# 24VloadSwitch.net
KiCad netlist of a schematic drawn in Altium Designer
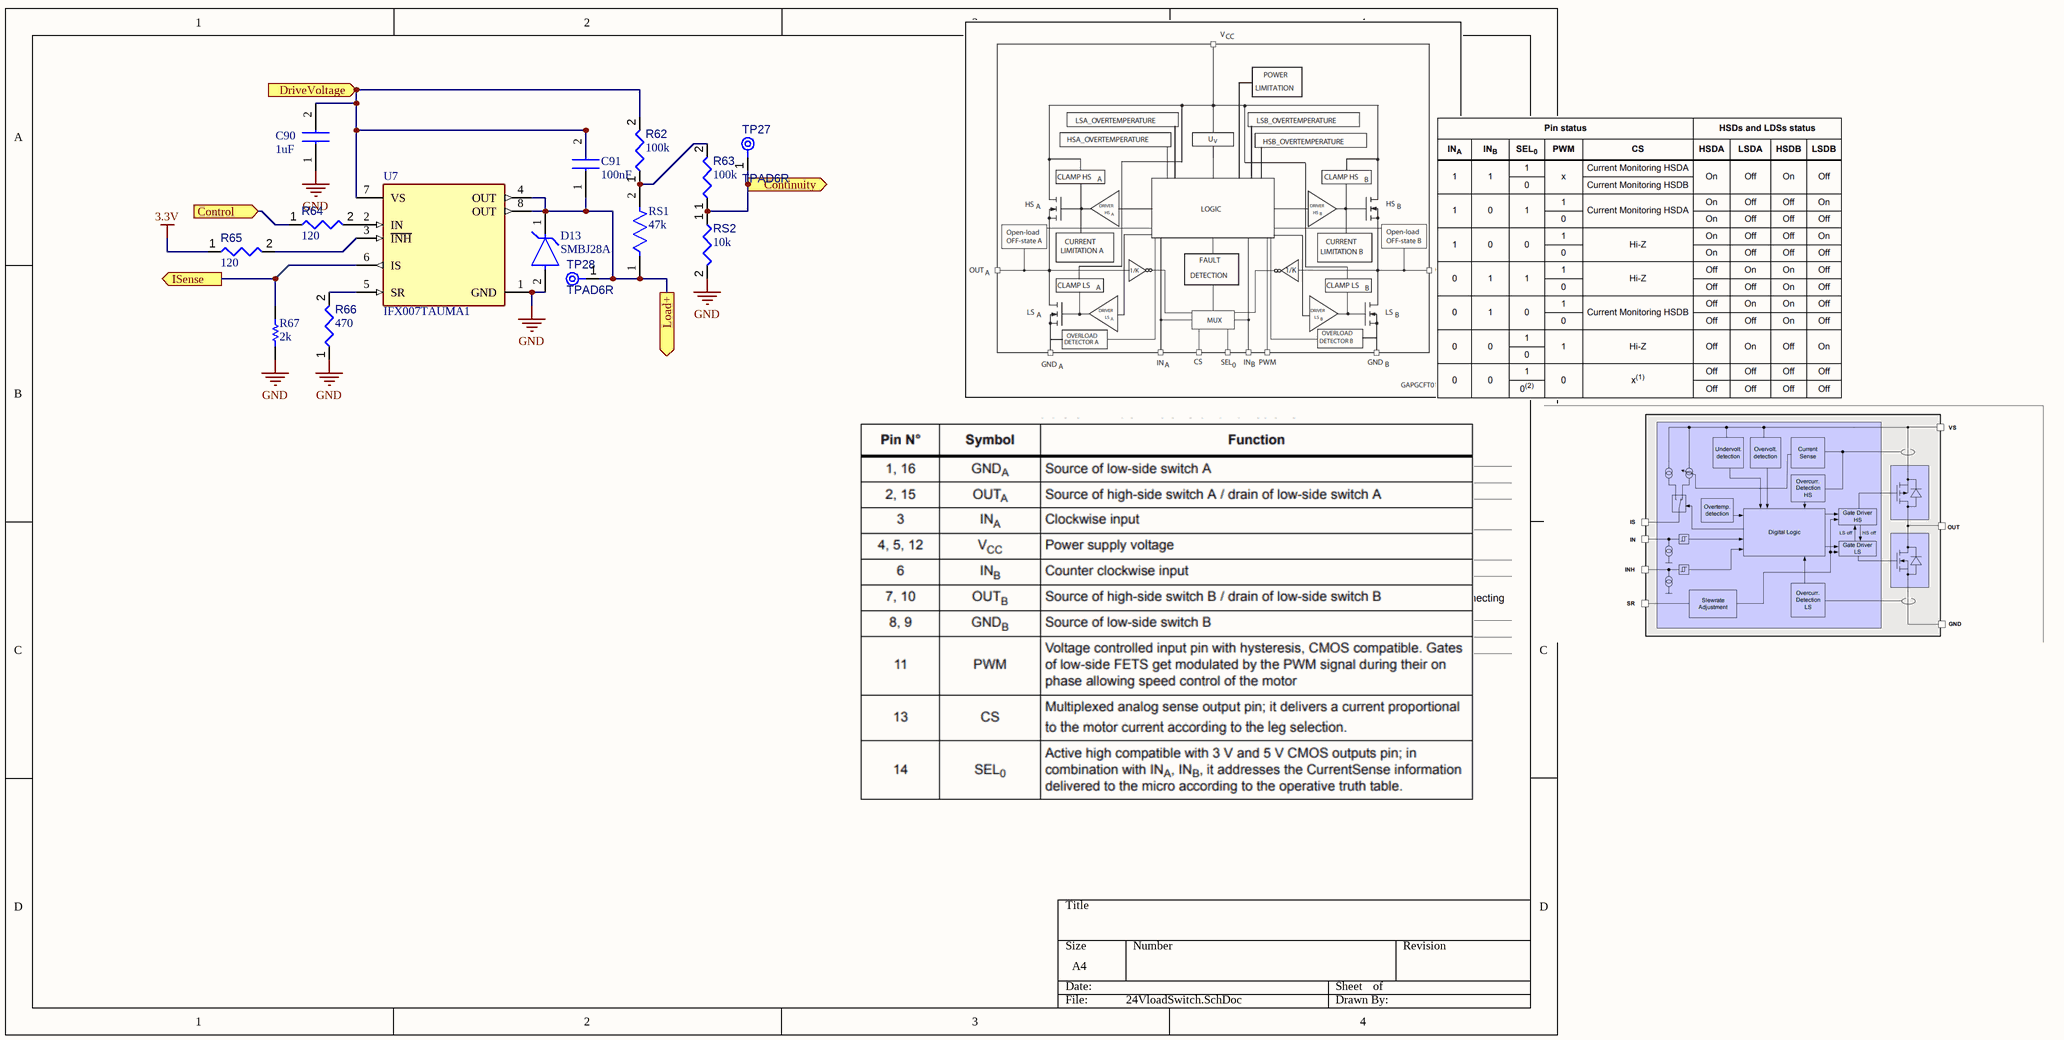
[diagram p0: 24VloadSwitch.SchDoc]

(export (version "E")
  (design (tool "Eeschema 10.0.6"))
  (components
    (comp (ref "C90")
      (value "1uF")
      (footprint "SamacSys:CAPC3216X180N")
      (description "1uF,1206, 50v")
      (fields
        (field (name "MANUFACTURER_PART_NUMBER") "CL31B105KBHNNNE")
        (field (name "MOUSER PART NUMBER") "187-CL31B105KBHNNNE")
      )
      (libsource (lib "*") (part "CL31B105KBHNNNE"))
    )
    (comp (ref "C91")
      (value "100nF")
      (footprint "SamacSys:CAPC1608X90N")
      (description "Capacitor,0603, 50V")
      (fields
        (field (name "MANUFACTURER_PART_NUMBER") "CC0603KRX7R9BB104")
        (field (name "MOUSER PART NUMBER") "603-CC603KRX7R9BB104")
      )
      (libsource (lib "*") (part "CC0603KRX7R9BB104"))
    )
    (comp (ref "D13")
      (value "SMBJ28A")
      (footprint "FP-SMBJ-MFG")
      (description "TVS DIODE 28V 45.4V DO214AA")
      (fields
        (field (name "MANUFACTURER") "Littelfuse Inc")
        (field (name "OCTOPART") "https://octopart.com/smbj28a-littelfuse-350790")
      )
      (libsource (lib "Altium Content Vault") (part "f813f71cba58e380607f5dd3caf9714"))
    )
    (comp (ref "R62")
      (value "100k")
      (footprint "RESC1608X55X25ML10T15")
      (description "Chip Resistor, 100 KOhm, +/- 1%, 0.1 W, -55 to 155 degC, 0603 (1608 Metric)")
      (fields (field (name "TOLERANCE") "1%") (field (name "POWER") "100mW"))
      (libsource (lib "Yuxuan chen") (part "RES-2"))
    )
    (comp (ref "R63")
      (value "100k")
      (footprint "RESC1608X55X25ML10T15")
      (description "Chip Resistor, 100 KOhm, +/- 1%, 0.1 W, -55 to 155 degC, 0603 (1608 Metric)")
      (fields (field (name "TOLERANCE") "1%") (field (name "POWER") "100mW"))
      (libsource (lib "Yuxuan chen") (part "RES-2"))
    )
    (comp (ref "R64")
      (value "120")
      (footprint "RESC0603(1608)_L")
      (description "Chip Resistor, 120 Ohms, +/-5 %, 0.1 W, -55 to 155 degC, 0603")
      (fields (field (name "POWER") "100mW") (field (name "TOLERANCE") "5%"))
      (libsource (lib "Yuxuan chen") (part "RES-2"))
    )
    (comp (ref "R65")
      (value "120")
      (footprint "RESC0603(1608)_L")
      (description "Chip Resistor, 120 Ohms, +/-5 %, 0.1 W, -55 to 155 degC, 0603")
      (fields (field (name "POWER") "100mW") (field (name "TOLERANCE") "5%"))
      (libsource (lib "Yuxuan chen") (part "RES-2"))
    )
    (comp (ref "R66")
      (value "470")
      (footprint "RESC0805(2012)_L")
      (description "470R 0.125W 5% 0805 (2012 Metric)  SMD")
      (fields (field (name "POWER") "125mW") (field (name "TOLERANCE") "5%"))
      (libsource (lib "Yuxuan chen") (part "470R5J"))
    )
    (comp (ref "R67")
      (value "2k")
      (footprint "RESC1609X50X30ML10T20")
      (description "CRCW06032K00FKEA")
      (fields (field (name "MANUFACTURER") "Vishay Dale"))
      (libsource (lib "Altium Content Vault") (part "RES"))
    )
    (comp (ref "RS1")
      (value "47k")
      (footprint "FP-CRCW0603-e3-IPC_B")
      (description "RES SMD 47K OHM 1% 1/10W 0603 CRCW060347K0FKEA")
      (fields (field (name "TOLERANCE") "1%"))
      (libsource (lib "Altium Content Vault") (part "1029c3af85768c4190bb7ad29bc67b5"))
    )
    (comp (ref "RS2")
      (value "10k")
      (footprint "RESC0402(1005)_L")
      (description "10K 0.063W 1% 0402 (1005 Metric)  SMD")
      (fields (field (name "POWER") "63mW") (field (name "TOLERANCE") "1%"))
      (libsource (lib "Yuxuan chen") (part "10KR2F"))
    )
    (comp (ref "TP27")
      (value "TPAD6R")
      (footprint "TP06R")
      (description "0.6mm round")
      (libsource (lib "Yuxuan chen") (part "CMP-001-0001-4"))
    )
    (comp (ref "TP28")
      (value "TPAD6R")
      (footprint "TP06R")
      (description "0.6mm round")
      (libsource (lib "Yuxuan chen") (part "CMP-001-0001-4"))
    )
    (comp (ref "U7")
      (value "IFX007TAUMA1")
      (footprint "FP-PG-TO263-7-MFG")
      (description "IC HALF-BRIDGE DRVR 2 CH TO263")
      (fields
        (field (name "MANUFACTURER") "Infineon")
        (field (name "OCTOPART") "https://octopart.com/ifx007tauma1-infineon-94578162")
      )
      (libsource (lib "Altium Content Vault") (part "468821ff50e4f9c8fccdb99b6782adb"))
    )
  )
  (nets
    (net (code "1") (name "/Continuity") (class "Default")
      (node (ref "R63") (pin "1") (pinfunction "1_1") (pintype "passive"))
      (node (ref "RS2") (pin "1") (pinfunction "1_1") (pintype "passive"))
      (node (ref "TP27") (pin "1") (pinfunction "TP_1") (pintype "passive"))
    )
    (net (code "2") (name "/Control") (class "Default")
      (node (ref "R64") (pin "1") (pinfunction "1_1") (pintype "passive"))
    )
    (net (code "3") (name "/DriveVoltage") (class "Default")
      (node (ref "C90") (pin "2") (pinfunction "2_2") (pintype "passive"))
      (node (ref "C91") (pin "2") (pinfunction "2_2") (pintype "passive"))
      (node (ref "R62") (pin "2") (pinfunction "2_2") (pintype "passive"))
      (node (ref "U7") (pin "7") (pinfunction "VS_7") (pintype "power_in"))
    )
    (net (code "4") (name "/ISense") (class "Default")
      (node (ref "R67") (pin "2") (pinfunction "2_2") (pintype "passive"))
      (node (ref "U7") (pin "6") (pinfunction "IS_6") (pintype "output"))
    )
    (net (code "5") (name "/Load+") (class "Default")
      (node (ref "C91") (pin "1") (pinfunction "1_1") (pintype "passive"))
      (node (ref "D13") (pin "1") (pinfunction "C_1") (pintype "passive"))
      (node (ref "RS1") (pin "1") (pinfunction "1_1") (pintype "passive"))
      (node (ref "TP28") (pin "1") (pinfunction "TP_1") (pintype "passive"))
      (node (ref "U7") (pin "4") (pinfunction "OUT_4") (pintype "output"))
      (node (ref "U7") (pin "8") (pinfunction "OUT_8") (pintype "output"))
    )
    (net (code "6") (name "3.3V") (class "Default")
      (node (ref "R65") (pin "1") (pinfunction "1_1") (pintype "passive"))
    )
    (net (code "7") (name "GND") (class "Default")
      (node (ref "C90") (pin "1") (pinfunction "1_1") (pintype "passive"))
      (node (ref "D13") (pin "2") (pinfunction "A_2") (pintype "passive"))
      (node (ref "R66") (pin "1") (pinfunction "1_1") (pintype "passive"))
      (node (ref "R67") (pin "1") (pinfunction "1_1") (pintype "passive"))
      (node (ref "RS2") (pin "2") (pinfunction "2_2") (pintype "passive"))
      (node (ref "U7") (pin "1") (pinfunction "GND_1") (pintype "power_in"))
    )
    (net (code "8") (name "Net-(R62-Pad1)") (class "Default")
      (node (ref "R62") (pin "1") (pinfunction "1_1") (pintype "passive"))
      (node (ref "R63") (pin "2") (pinfunction "2_2") (pintype "passive"))
      (node (ref "RS1") (pin "2") (pinfunction "2_2") (pintype "passive"))
    )
    (net (code "9") (name "Net-(U7-IN)") (class "Default")
      (node (ref "R64") (pin "2") (pinfunction "2_2") (pintype "passive"))
      (node (ref "U7") (pin "2") (pinfunction "IN_2") (pintype "input"))
    )
    (net (code "10") (name "Net-(U7-SR)") (class "Default")
      (node (ref "R66") (pin "2") (pinfunction "2_2") (pintype "passive"))
      (node (ref "U7") (pin "5") (pinfunction "SR_5") (pintype "input"))
    )
    (net (code "11") (name "Net-(U7-~{INH})") (class "Default")
      (node (ref "R65") (pin "2") (pinfunction "2_2") (pintype "passive"))
      (node (ref "U7") (pin "3") (pinfunction "~{INH}_3") (pintype "input"))
    )
  )
)
